# driver_controller.net
KiCad netlist of a schematic drawn in EAGLE
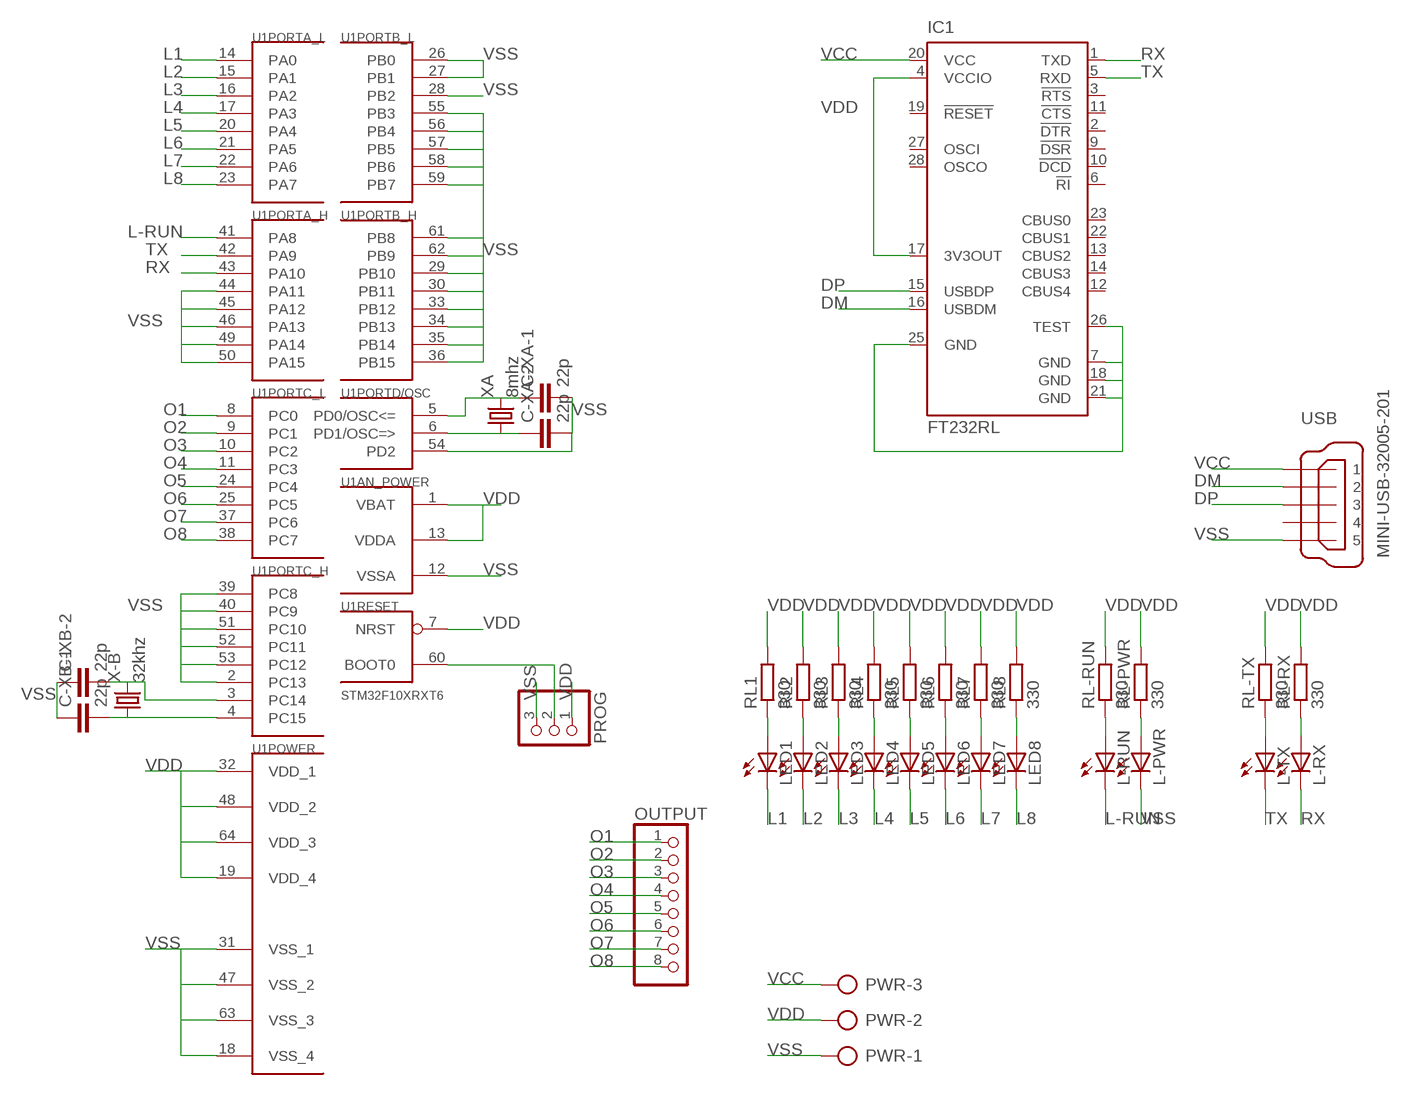
[diagram p0: schematic, sheet 1]

(export (version "E")
  (design (tool "Eeschema 10.0.6"))
  (components
    (comp (ref "C-XA-1")
      (value "22p")
      (footprint "eagle-import:C1206")
      (libsource (lib "eagle-import") (part "C-EUC1206"))
    )
    (comp (ref "C-XA-2")
      (value "22p")
      (footprint "eagle-import:C1206")
      (libsource (lib "eagle-import") (part "C-EUC1206"))
    )
    (comp (ref "C-XB-1")
      (value "22p")
      (footprint "eagle-import:C1206")
      (libsource (lib "eagle-import") (part "C-EUC1206"))
    )
    (comp (ref "C-XB-2")
      (value "22p")
      (footprint "eagle-import:C1206")
      (libsource (lib "eagle-import") (part "C-EUC1206"))
    )
    (comp (ref "IC1")
      (value "FT232RL")
      (footprint "eagle-import:SSOP28")
      (libsource (lib "eagle-import") (part "FT232RL"))
    )
    (comp (ref "L-PWR")
      (value "LEDSML1206")
      (footprint "eagle-import:SML1206")
      (libsource (lib "eagle-import") (part "LEDSML1206"))
    )
    (comp (ref "L-RUN")
      (value "LEDSML1206")
      (footprint "eagle-import:SML1206")
      (libsource (lib "eagle-import") (part "LEDSML1206"))
    )
    (comp (ref "L-RX")
      (value "LEDSML1206")
      (footprint "eagle-import:SML1206")
      (libsource (lib "eagle-import") (part "LEDSML1206"))
    )
    (comp (ref "L-TX")
      (value "LEDSML1206")
      (footprint "eagle-import:SML1206")
      (libsource (lib "eagle-import") (part "LEDSML1206"))
    )
    (comp (ref "LED1")
      (value "LEDSML1206")
      (footprint "eagle-import:SML1206")
      (libsource (lib "eagle-import") (part "LEDSML1206"))
    )
    (comp (ref "LED2")
      (value "LEDSML1206")
      (footprint "eagle-import:SML1206")
      (libsource (lib "eagle-import") (part "LEDSML1206"))
    )
    (comp (ref "LED3")
      (value "LEDSML1206")
      (footprint "eagle-import:SML1206")
      (libsource (lib "eagle-import") (part "LEDSML1206"))
    )
    (comp (ref "LED4")
      (value "LEDSML1206")
      (footprint "eagle-import:SML1206")
      (libsource (lib "eagle-import") (part "LEDSML1206"))
    )
    (comp (ref "LED5")
      (value "LEDSML1206")
      (footprint "eagle-import:SML1206")
      (libsource (lib "eagle-import") (part "LEDSML1206"))
    )
    (comp (ref "LED6")
      (value "LEDSML1206")
      (footprint "eagle-import:SML1206")
      (libsource (lib "eagle-import") (part "LEDSML1206"))
    )
    (comp (ref "LED7")
      (value "LEDSML1206")
      (footprint "eagle-import:SML1206")
      (libsource (lib "eagle-import") (part "LEDSML1206"))
    )
    (comp (ref "LED8")
      (value "LEDSML1206")
      (footprint "eagle-import:SML1206")
      (libsource (lib "eagle-import") (part "LEDSML1206"))
    )
    (comp (ref "OUTPUT")
      (value "PINHD-1X8")
      (footprint "eagle-import:1X08")
      (libsource (lib "eagle-import") (part "PINHD-1X8"))
    )
    (comp (ref "PROG")
      (value "PINHD-1X3")
      (footprint "eagle-import:1X03")
      (libsource (lib "eagle-import") (part "PINHD-1X3"))
    )
    (comp (ref "PWR")
      (value "AK300/3")
      (footprint "eagle-import:AK300_3")
      (libsource (lib "eagle-import") (part "AK300/3"))
    )
    (comp (ref "RL-PWR")
      (value "330")
      (footprint "eagle-import:R1206")
      (libsource (lib "eagle-import") (part "R-EU_R1206"))
    )
    (comp (ref "RL-RUN")
      (value "330")
      (footprint "eagle-import:R1206")
      (libsource (lib "eagle-import") (part "R-EU_R1206"))
    )
    (comp (ref "RL-RX")
      (value "330")
      (footprint "eagle-import:R1206")
      (libsource (lib "eagle-import") (part "R-EU_R1206"))
    )
    (comp (ref "RL-TX")
      (value "330")
      (footprint "eagle-import:R1206")
      (libsource (lib "eagle-import") (part "R-EU_R1206"))
    )
    (comp (ref "RL1")
      (value "330")
      (footprint "eagle-import:R1206")
      (libsource (lib "eagle-import") (part "R-EU_R1206"))
    )
    (comp (ref "RL2")
      (value "330")
      (footprint "eagle-import:R1206")
      (libsource (lib "eagle-import") (part "R-EU_R1206"))
    )
    (comp (ref "RL3")
      (value "330")
      (footprint "eagle-import:R1206")
      (libsource (lib "eagle-import") (part "R-EU_R1206"))
    )
    (comp (ref "RL4")
      (value "330")
      (footprint "eagle-import:R1206")
      (libsource (lib "eagle-import") (part "R-EU_R1206"))
    )
    (comp (ref "RL5")
      (value "330")
      (footprint "eagle-import:R1206")
      (libsource (lib "eagle-import") (part "R-EU_R1206"))
    )
    (comp (ref "RL6")
      (value "330")
      (footprint "eagle-import:R1206")
      (libsource (lib "eagle-import") (part "R-EU_R1206"))
    )
    (comp (ref "RL7")
      (value "330")
      (footprint "eagle-import:R1206")
      (libsource (lib "eagle-import") (part "R-EU_R1206"))
    )
    (comp (ref "RL8")
      (value "330")
      (footprint "eagle-import:R1206")
      (libsource (lib "eagle-import") (part "R-EU_R1206"))
    )
    (comp (ref "U1")
      (value "STM32F10XRXT6")
      (footprint "eagle-import:TQFP64")
      (libsource (lib "eagle-import") (part "STM32F10XRXT6"))
    )
    (comp (ref "USB")
      (value "MINI-USB-32005-201")
      (footprint "eagle-import:32005-201")
      (libsource (lib "eagle-import") (part "MINI-USB-32005-201"))
    )
    (comp (ref "X-B")
      (value "32khz")
      (footprint "eagle-import:TC26V")
      (libsource (lib "eagle-import") (part "CRYSTALTC26V"))
    )
    (comp (ref "XA")
      (value "8mhz")
      (footprint "eagle-import:HC49_S")
      (libsource (lib "eagle-import") (part "CRYSTALHC49S"))
    )
  )
  (nets
    (net (code "1") (name "/DM") (class "Default")
      (node (ref "IC1") (pin "16") (pinfunction "USBDM_16") (pintype "bidirectional"))
      (node (ref "USB") (pin "2") (pinfunction "2_2") (pintype "passive"))
    )
    (net (code "2") (name "/DP") (class "Default")
      (node (ref "IC1") (pin "15") (pinfunction "USBDP_15") (pintype "bidirectional"))
      (node (ref "USB") (pin "3") (pinfunction "3_3") (pintype "passive"))
    )
    (net (code "3") (name "/L-RUN") (class "Default")
      (node (ref "L-RUN") (pin "C") (pinfunction "C_C") (pintype "passive"))
      (node (ref "U1") (pin "41") (pinfunction "PA8_41") (pintype "bidirectional"))
    )
    (net (code "4") (name "/L1") (class "Default")
      (node (ref "LED1") (pin "C") (pinfunction "C_C") (pintype "passive"))
      (node (ref "U1") (pin "14") (pinfunction "PA0_14") (pintype "bidirectional"))
    )
    (net (code "5") (name "/L2") (class "Default")
      (node (ref "LED2") (pin "C") (pinfunction "C_C") (pintype "passive"))
      (node (ref "U1") (pin "15") (pinfunction "PA1_15") (pintype "bidirectional"))
    )
    (net (code "6") (name "/L3") (class "Default")
      (node (ref "LED3") (pin "C") (pinfunction "C_C") (pintype "passive"))
      (node (ref "U1") (pin "16") (pinfunction "PA2_16") (pintype "bidirectional"))
    )
    (net (code "7") (name "/L4") (class "Default")
      (node (ref "LED4") (pin "C") (pinfunction "C_C") (pintype "passive"))
      (node (ref "U1") (pin "17") (pinfunction "PA3_17") (pintype "bidirectional"))
    )
    (net (code "8") (name "/L5") (class "Default")
      (node (ref "LED5") (pin "C") (pinfunction "C_C") (pintype "passive"))
      (node (ref "U1") (pin "20") (pinfunction "PA4_20") (pintype "bidirectional"))
    )
    (net (code "9") (name "/L6") (class "Default")
      (node (ref "LED6") (pin "C") (pinfunction "C_C") (pintype "passive"))
      (node (ref "U1") (pin "21") (pinfunction "PA5_21") (pintype "bidirectional"))
    )
    (net (code "10") (name "/L7") (class "Default")
      (node (ref "LED7") (pin "C") (pinfunction "C_C") (pintype "passive"))
      (node (ref "U1") (pin "22") (pinfunction "PA6_22") (pintype "bidirectional"))
    )
    (net (code "11") (name "/L8") (class "Default")
      (node (ref "LED8") (pin "C") (pinfunction "C_C") (pintype "passive"))
      (node (ref "U1") (pin "23") (pinfunction "PA7_23") (pintype "bidirectional"))
    )
    (net (code "12") (name "/O1") (class "Default")
      (node (ref "OUTPUT") (pin "1") (pinfunction "1_1") (pintype "passive"))
      (node (ref "U1") (pin "8") (pinfunction "PC0_8") (pintype "bidirectional"))
    )
    (net (code "13") (name "/O2") (class "Default")
      (node (ref "OUTPUT") (pin "2") (pinfunction "2_2") (pintype "passive"))
      (node (ref "U1") (pin "9") (pinfunction "PC1_9") (pintype "bidirectional"))
    )
    (net (code "14") (name "/O3") (class "Default")
      (node (ref "OUTPUT") (pin "3") (pinfunction "3_3") (pintype "passive"))
      (node (ref "U1") (pin "10") (pinfunction "PC2_10") (pintype "bidirectional"))
    )
    (net (code "15") (name "/O4") (class "Default")
      (node (ref "OUTPUT") (pin "4") (pinfunction "4_4") (pintype "passive"))
      (node (ref "U1") (pin "11") (pinfunction "PC3_11") (pintype "bidirectional"))
    )
    (net (code "16") (name "/O5") (class "Default")
      (node (ref "OUTPUT") (pin "5") (pinfunction "5_5") (pintype "passive"))
      (node (ref "U1") (pin "24") (pinfunction "PC4_24") (pintype "bidirectional"))
    )
    (net (code "17") (name "/O6") (class "Default")
      (node (ref "OUTPUT") (pin "6") (pinfunction "6_6") (pintype "passive"))
      (node (ref "U1") (pin "25") (pinfunction "PC5_25") (pintype "bidirectional"))
    )
    (net (code "18") (name "/O7") (class "Default")
      (node (ref "OUTPUT") (pin "7") (pinfunction "7_7") (pintype "passive"))
      (node (ref "U1") (pin "37") (pinfunction "PC6_37") (pintype "bidirectional"))
    )
    (net (code "19") (name "/O8") (class "Default")
      (node (ref "OUTPUT") (pin "8") (pinfunction "8_8") (pintype "passive"))
      (node (ref "U1") (pin "38") (pinfunction "PC7_38") (pintype "bidirectional"))
    )
    (net (code "20") (name "/RX") (class "Default")
      (node (ref "IC1") (pin "1") (pinfunction "TXD_1") (pintype "output"))
      (node (ref "L-RX") (pin "C") (pinfunction "C_C") (pintype "passive"))
      (node (ref "U1") (pin "43") (pinfunction "PA10_43") (pintype "bidirectional"))
    )
    (net (code "21") (name "/TX") (class "Default")
      (node (ref "IC1") (pin "5") (pinfunction "RXD_5") (pintype "input"))
      (node (ref "L-TX") (pin "C") (pinfunction "C_C") (pintype "passive"))
      (node (ref "U1") (pin "42") (pinfunction "PA9_42") (pintype "bidirectional"))
    )
    (net (code "22") (name "/VCC") (class "Default")
      (node (ref "IC1") (pin "20") (pinfunction "VCC_20") (pintype "power_in"))
      (node (ref "PWR") (pin "3") (pinfunction "KL_3") (pintype "passive"))
      (node (ref "USB") (pin "1") (pinfunction "1_1") (pintype "passive"))
    )
    (net (code "23") (name "/VDD") (class "Default")
      (node (ref "IC1") (pin "17") (pinfunction "3V3OUT_17") (pintype "output"))
      (node (ref "IC1") (pin "4") (pinfunction "VCCIO_4") (pintype "power_in"))
      (node (ref "PROG") (pin "1") (pinfunction "1_1") (pintype "passive"))
      (node (ref "PWR") (pin "2") (pinfunction "KL_2") (pintype "passive"))
      (node (ref "RL-PWR") (pin "2") (pinfunction "2_2") (pintype "passive"))
      (node (ref "RL-RUN") (pin "2") (pinfunction "2_2") (pintype "passive"))
      (node (ref "RL-RX") (pin "2") (pinfunction "2_2") (pintype "passive"))
      (node (ref "RL-TX") (pin "2") (pinfunction "2_2") (pintype "passive"))
      (node (ref "RL1") (pin "2") (pinfunction "2_2") (pintype "passive"))
      (node (ref "RL2") (pin "2") (pinfunction "2_2") (pintype "passive"))
      (node (ref "RL3") (pin "2") (pinfunction "2_2") (pintype "passive"))
      (node (ref "RL4") (pin "2") (pinfunction "2_2") (pintype "passive"))
      (node (ref "RL5") (pin "2") (pinfunction "2_2") (pintype "passive"))
      (node (ref "RL6") (pin "2") (pinfunction "2_2") (pintype "passive"))
      (node (ref "RL7") (pin "2") (pinfunction "2_2") (pintype "passive"))
      (node (ref "RL8") (pin "2") (pinfunction "2_2") (pintype "passive"))
      (node (ref "U1") (pin "1") (pinfunction "VBAT_1") (pintype "power_in"))
      (node (ref "U1") (pin "13") (pinfunction "VDDA_13") (pintype "power_in"))
      (node (ref "U1") (pin "19") (pinfunction "VDD_4_19") (pintype "power_in"))
      (node (ref "U1") (pin "32") (pinfunction "VDD_1_32") (pintype "power_in"))
      (node (ref "U1") (pin "48") (pinfunction "VDD_2_48") (pintype "power_in"))
      (node (ref "U1") (pin "64") (pinfunction "VDD_3_64") (pintype "power_in"))
      (node (ref "U1") (pin "7") (pinfunction "NRST_7") (pintype "input"))
    )
    (net (code "24") (name "/VSS") (class "Default")
      (node (ref "C-XA-1") (pin "2") (pinfunction "2_2") (pintype "passive"))
      (node (ref "C-XA-2") (pin "2") (pinfunction "2_2") (pintype "passive"))
      (node (ref "C-XB-1") (pin "1") (pinfunction "1_1") (pintype "passive"))
      (node (ref "C-XB-2") (pin "1") (pinfunction "1_1") (pintype "passive"))
      (node (ref "IC1") (pin "18") (pinfunction "GND_18") (pintype "power_in"))
      (node (ref "IC1") (pin "21") (pinfunction "GND_21") (pintype "power_in"))
      (node (ref "IC1") (pin "25") (pinfunction "GND_25") (pintype "power_in"))
      (node (ref "IC1") (pin "26") (pinfunction "TEST_26") (pintype "input"))
      (node (ref "IC1") (pin "7") (pinfunction "GND_7") (pintype "power_in"))
      (node (ref "L-PWR") (pin "C") (pinfunction "C_C") (pintype "passive"))
      (node (ref "PROG") (pin "3") (pinfunction "3_3") (pintype "passive"))
      (node (ref "PWR") (pin "1") (pinfunction "KL_1") (pintype "passive"))
      (node (ref "U1") (pin "12") (pinfunction "VSSA_12") (pintype "power_in"))
      (node (ref "U1") (pin "18") (pinfunction "VSS_4_18") (pintype "power_in"))
      (node (ref "U1") (pin "2") (pinfunction "PC13_2") (pintype "bidirectional"))
      (node (ref "U1") (pin "26") (pinfunction "PB0_26") (pintype "bidirectional"))
      (node (ref "U1") (pin "27") (pinfunction "PB1_27") (pintype "bidirectional"))
      (node (ref "U1") (pin "28") (pinfunction "PB2_28") (pintype "bidirectional"))
      (node (ref "U1") (pin "29") (pinfunction "PB10_29") (pintype "bidirectional"))
      (node (ref "U1") (pin "30") (pinfunction "PB11_30") (pintype "bidirectional"))
      (node (ref "U1") (pin "31") (pinfunction "VSS_1_31") (pintype "power_in"))
      (node (ref "U1") (pin "33") (pinfunction "PB12_33") (pintype "bidirectional"))
      (node (ref "U1") (pin "34") (pinfunction "PB13_34") (pintype "bidirectional"))
      (node (ref "U1") (pin "35") (pinfunction "PB14_35") (pintype "bidirectional"))
      (node (ref "U1") (pin "36") (pinfunction "PB15_36") (pintype "bidirectional"))
      (node (ref "U1") (pin "39") (pinfunction "PC8_39") (pintype "bidirectional"))
      (node (ref "U1") (pin "40") (pinfunction "PC9_40") (pintype "bidirectional"))
      (node (ref "U1") (pin "44") (pinfunction "PA11_44") (pintype "bidirectional"))
      (node (ref "U1") (pin "45") (pinfunction "PA12_45") (pintype "bidirectional"))
      (node (ref "U1") (pin "46") (pinfunction "PA13_46") (pintype "bidirectional"))
      (node (ref "U1") (pin "47") (pinfunction "VSS_2_47") (pintype "power_in"))
      (node (ref "U1") (pin "49") (pinfunction "PA14_49") (pintype "bidirectional"))
      (node (ref "U1") (pin "50") (pinfunction "PA15_50") (pintype "bidirectional"))
      (node (ref "U1") (pin "51") (pinfunction "PC10_51") (pintype "bidirectional"))
      (node (ref "U1") (pin "52") (pinfunction "PC11_52") (pintype "bidirectional"))
      (node (ref "U1") (pin "53") (pinfunction "PC12_53") (pintype "bidirectional"))
      (node (ref "U1") (pin "54") (pinfunction "PD2_54") (pintype "bidirectional"))
      (node (ref "U1") (pin "55") (pinfunction "PB3_55") (pintype "bidirectional"))
      (node (ref "U1") (pin "56") (pinfunction "PB4_56") (pintype "bidirectional"))
      (node (ref "U1") (pin "57") (pinfunction "PB5_57") (pintype "bidirectional"))
      (node (ref "U1") (pin "58") (pinfunction "PB6_58") (pintype "bidirectional"))
      (node (ref "U1") (pin "59") (pinfunction "PB7_59") (pintype "bidirectional"))
      (node (ref "U1") (pin "61") (pinfunction "PB8_61") (pintype "bidirectional"))
      (node (ref "U1") (pin "62") (pinfunction "PB9_62") (pintype "bidirectional"))
      (node (ref "U1") (pin "63") (pinfunction "VSS_3_63") (pintype "power_in"))
      (node (ref "USB") (pin "5") (pinfunction "5_5") (pintype "passive"))
    )
    (net (code "25") (name "Net-(L-PWR-PadA)") (class "Default")
      (node (ref "L-PWR") (pin "A") (pinfunction "A_A") (pintype "passive"))
      (node (ref "RL-PWR") (pin "1") (pinfunction "1_1") (pintype "passive"))
    )
    (net (code "26") (name "Net-(L-RUN-PadA)") (class "Default")
      (node (ref "L-RUN") (pin "A") (pinfunction "A_A") (pintype "passive"))
      (node (ref "RL-RUN") (pin "1") (pinfunction "1_1") (pintype "passive"))
    )
    (net (code "27") (name "Net-(L-RX-PadA)") (class "Default")
      (node (ref "L-RX") (pin "A") (pinfunction "A_A") (pintype "passive"))
      (node (ref "RL-RX") (pin "1") (pinfunction "1_1") (pintype "passive"))
    )
    (net (code "28") (name "Net-(L-TX-PadA)") (class "Default")
      (node (ref "L-TX") (pin "A") (pinfunction "A_A") (pintype "passive"))
      (node (ref "RL-TX") (pin "1") (pinfunction "1_1") (pintype "passive"))
    )
    (net (code "29") (name "Net-(LED1-PadA)") (class "Default")
      (node (ref "LED1") (pin "A") (pinfunction "A_A") (pintype "passive"))
      (node (ref "RL1") (pin "1") (pinfunction "1_1") (pintype "passive"))
    )
    (net (code "30") (name "Net-(LED2-PadA)") (class "Default")
      (node (ref "LED2") (pin "A") (pinfunction "A_A") (pintype "passive"))
      (node (ref "RL2") (pin "1") (pinfunction "1_1") (pintype "passive"))
    )
    (net (code "31") (name "Net-(LED3-PadA)") (class "Default")
      (node (ref "LED3") (pin "A") (pinfunction "A_A") (pintype "passive"))
      (node (ref "RL3") (pin "1") (pinfunction "1_1") (pintype "passive"))
    )
    (net (code "32") (name "Net-(LED4-PadA)") (class "Default")
      (node (ref "LED4") (pin "A") (pinfunction "A_A") (pintype "passive"))
      (node (ref "RL4") (pin "1") (pinfunction "1_1") (pintype "passive"))
    )
    (net (code "33") (name "Net-(LED5-PadA)") (class "Default")
      (node (ref "LED5") (pin "A") (pinfunction "A_A") (pintype "passive"))
      (node (ref "RL5") (pin "1") (pinfunction "1_1") (pintype "passive"))
    )
    (net (code "34") (name "Net-(LED6-PadA)") (class "Default")
      (node (ref "LED6") (pin "A") (pinfunction "A_A") (pintype "passive"))
      (node (ref "RL6") (pin "1") (pinfunction "1_1") (pintype "passive"))
    )
    (net (code "35") (name "Net-(LED7-PadA)") (class "Default")
      (node (ref "LED7") (pin "A") (pinfunction "A_A") (pintype "passive"))
      (node (ref "RL7") (pin "1") (pinfunction "1_1") (pintype "passive"))
    )
    (net (code "36") (name "Net-(LED8-PadA)") (class "Default")
      (node (ref "LED8") (pin "A") (pinfunction "A_A") (pintype "passive"))
      (node (ref "RL8") (pin "1") (pinfunction "1_1") (pintype "passive"))
    )
    (net (code "37") (name "Net-(U1F-PC14)") (class "Default")
      (node (ref "C-XB-2") (pin "2") (pinfunction "2_2") (pintype "passive"))
      (node (ref "U1") (pin "3") (pinfunction "PC14_3") (pintype "bidirectional"))
      (node (ref "X-B") (pin "2") (pinfunction "2_2") (pintype "passive"))
    )
    (net (code "38") (name "Net-(U1F-PC15)") (class "Default")
      (node (ref "C-XB-1") (pin "2") (pinfunction "2_2") (pintype "passive"))
      (node (ref "U1") (pin "4") (pinfunction "PC15_4") (pintype "bidirectional"))
      (node (ref "X-B") (pin "1") (pinfunction "1_1") (pintype "passive"))
    )
    (net (code "39") (name "Net-(U1H-PD0{slash}OSC<=)") (class "Default")
      (node (ref "C-XA-1") (pin "1") (pinfunction "1_1") (pintype "passive"))
      (node (ref "U1") (pin "5") (pinfunction "PD0/OSC<=_5") (pintype "bidirectional"))
      (node (ref "XA") (pin "2") (pinfunction "2_2") (pintype "passive"))
    )
    (net (code "40") (name "Net-(U1H-PD1{slash}OSC=>)") (class "Default")
      (node (ref "C-XA-2") (pin "1") (pinfunction "1_1") (pintype "passive"))
      (node (ref "U1") (pin "6") (pinfunction "PD1/OSC=>_6") (pintype "bidirectional"))
      (node (ref "XA") (pin "1") (pinfunction "1_1") (pintype "passive"))
    )
    (net (code "41") (name "Net-(U1J-BOOT0)") (class "Default")
      (node (ref "PROG") (pin "2") (pinfunction "2_2") (pintype "passive"))
      (node (ref "U1") (pin "60") (pinfunction "BOOT0_60") (pintype "input"))
    )
    (net (code "42") (name "unconnected-(IC1-CBUS0-Pad23)") (class "Default")
      (node (ref "IC1") (pin "23") (pinfunction "CBUS0_23") (pintype "bidirectional"))
    )
    (net (code "43") (name "unconnected-(IC1-CBUS1-Pad22)") (class "Default")
      (node (ref "IC1") (pin "22") (pinfunction "CBUS1_22") (pintype "bidirectional"))
    )
    (net (code "44") (name "unconnected-(IC1-CBUS2-Pad13)") (class "Default")
      (node (ref "IC1") (pin "13") (pinfunction "CBUS2_13") (pintype "bidirectional"))
    )
    (net (code "45") (name "unconnected-(IC1-CBUS3-Pad14)") (class "Default")
      (node (ref "IC1") (pin "14") (pinfunction "CBUS3_14") (pintype "bidirectional"))
    )
    (net (code "46") (name "unconnected-(IC1-CBUS4-Pad12)") (class "Default")
      (node (ref "IC1") (pin "12") (pinfunction "CBUS4_12") (pintype "bidirectional"))
    )
    (net (code "47") (name "unconnected-(IC1-OSCI-Pad27)") (class "Default")
      (node (ref "IC1") (pin "27") (pinfunction "OSCI_27") (pintype "input"))
    )
    (net (code "48") (name "unconnected-(IC1-OSCO-Pad28)") (class "Default")
      (node (ref "IC1") (pin "28") (pinfunction "OSCO_28") (pintype "output"))
    )
    (net (code "49") (name "unconnected-(IC1-~{CTS}-Pad11)") (class "Default")
      (node (ref "IC1") (pin "11") (pinfunction "~{CTS}_11") (pintype "input"))
    )
    (net (code "50") (name "unconnected-(IC1-~{DCD}-Pad10)") (class "Default")
      (node (ref "IC1") (pin "10") (pinfunction "~{DCD}_10") (pintype "input"))
    )
    (net (code "51") (name "unconnected-(IC1-~{DSR}-Pad9)") (class "Default")
      (node (ref "IC1") (pin "9") (pinfunction "~{DSR}_9") (pintype "input"))
    )
    (net (code "52") (name "unconnected-(IC1-~{DTR}-Pad2)") (class "Default")
      (node (ref "IC1") (pin "2") (pinfunction "~{DTR}_2") (pintype "output"))
    )
    (net (code "53") (name "unconnected-(IC1-~{RESET}-Pad19)") (class "Default")
      (node (ref "IC1") (pin "19") (pinfunction "~{RESET}_19") (pintype "input"))
    )
    (net (code "54") (name "unconnected-(IC1-~{RI}-Pad6)") (class "Default")
      (node (ref "IC1") (pin "6") (pinfunction "~{RI}_6") (pintype "input"))
    )
    (net (code "55") (name "unconnected-(IC1-~{RTS}-Pad3)") (class "Default")
      (node (ref "IC1") (pin "3") (pinfunction "~{RTS}_3") (pintype "output"))
    )
    (net (code "56") (name "unconnected-(USB-Pad4)") (class "Default")
      (node (ref "USB") (pin "4") (pinfunction "4_4") (pintype "passive"))
    )
  )
)
